# OSO-MISC-21-020_Temperature_GPIO_Board.net
KiCad netlist of a schematic drawn in EAGLE
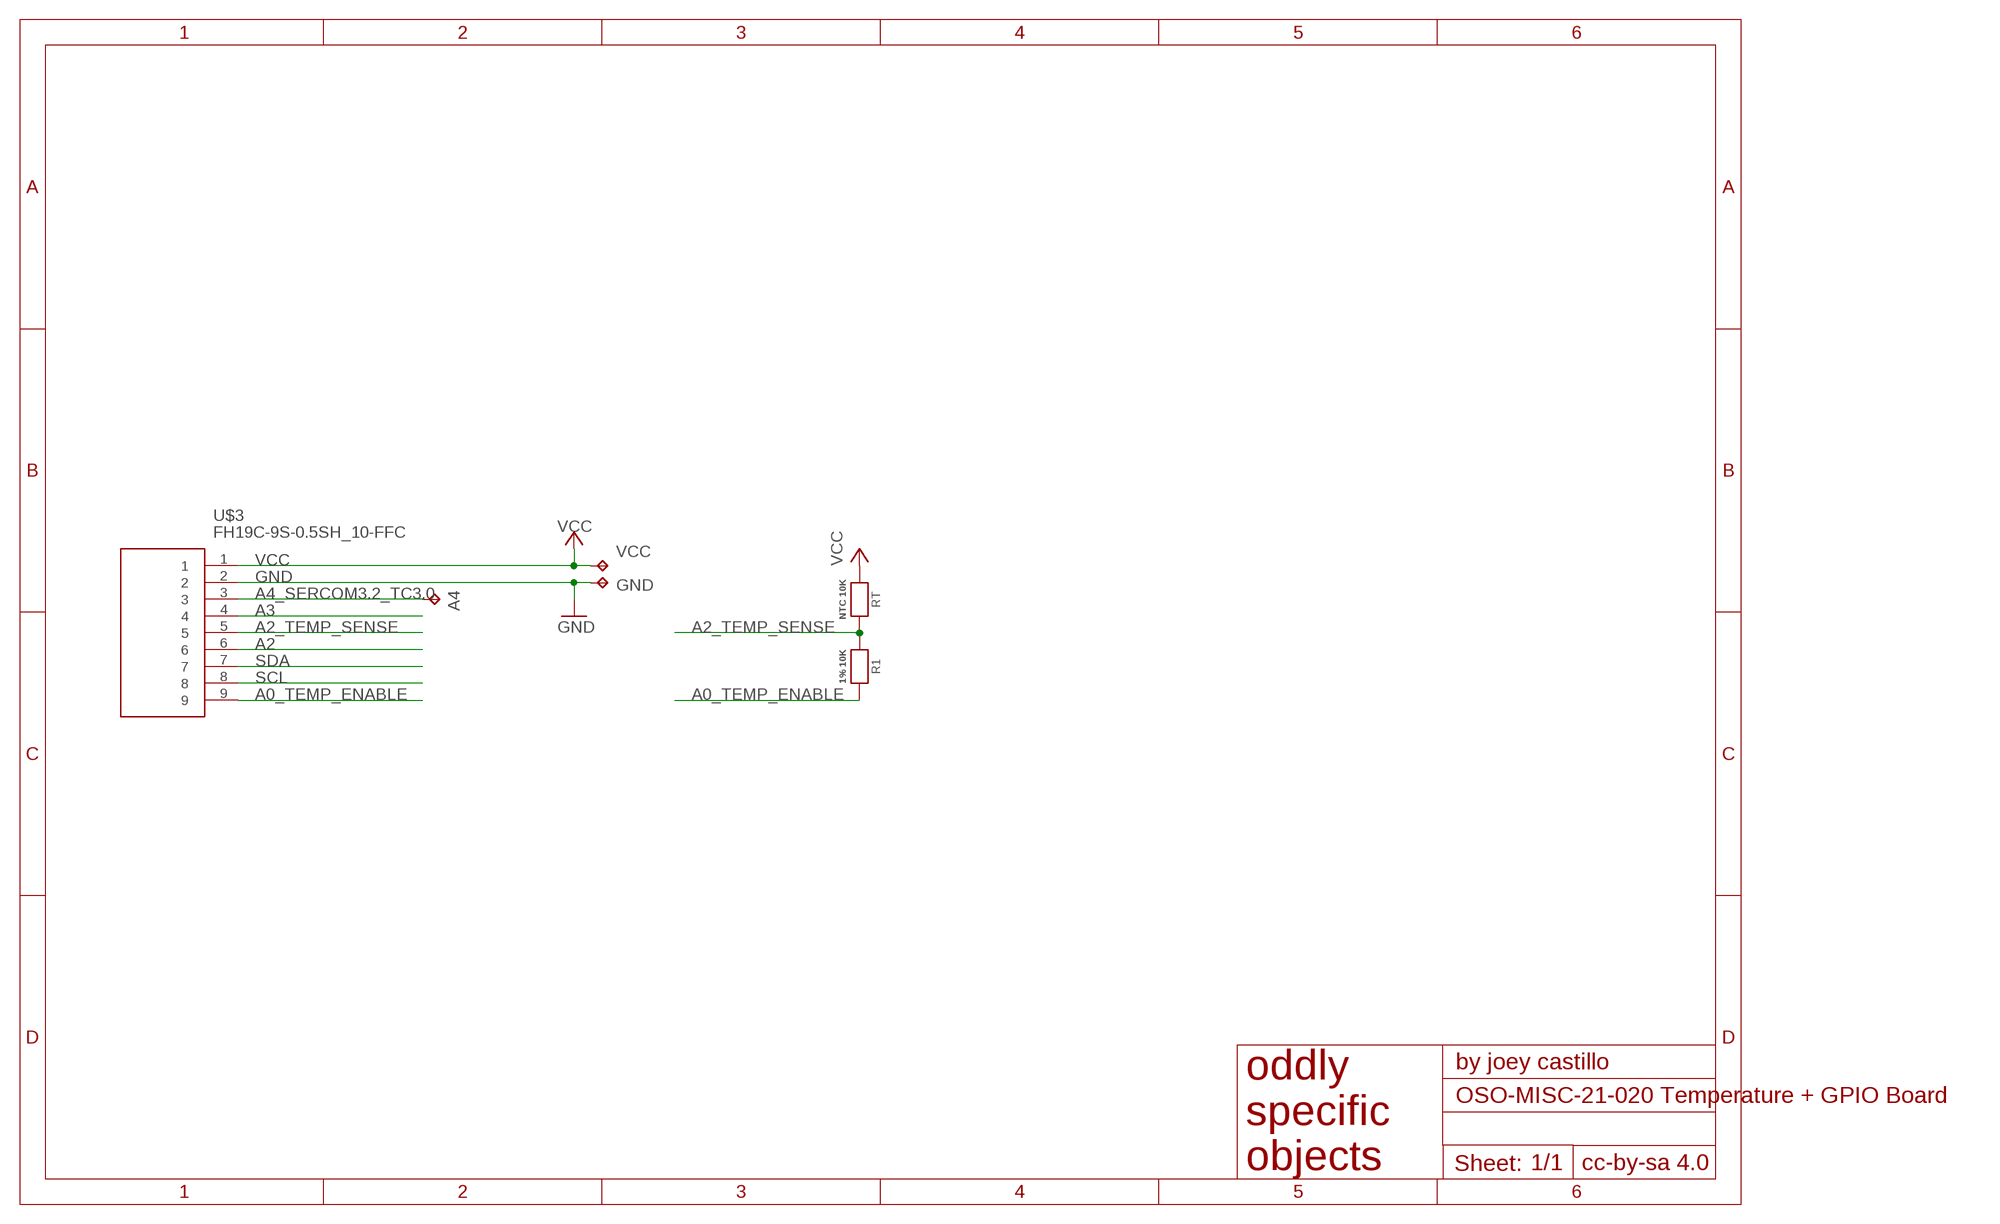
[diagram p0: schematic, sheet 1]

(export (version "E")
  (design (tool "Eeschema 10.0.6"))
  (components
    (comp (ref "A4")
      (value "TPB1,27")
      (footprint "eagle-import:B1,27")
      (libsource (lib "eagle-import") (part "TPB1,27"))
    )
    (comp (ref "GND")
      (value "TPB1,27")
      (footprint "eagle-import:B1,27")
      (libsource (lib "eagle-import") (part "TPB1,27"))
    )
    (comp (ref "R1")
      (value "1% 10K")
      (footprint "eagle-import:_0603MP")
      (libsource (lib "eagle-import") (part "RESISTOR_0603MP"))
    )
    (comp (ref "RT")
      (value "NTC 10K")
      (footprint "eagle-import:_0603")
      (libsource (lib "eagle-import") (part "RESISTOR_0603"))
    )
    (comp (ref "U$3")
      (value "FH19C-9S-0.5SH_10-FFC")
      (footprint "eagle-import:FH19C9S05SH10-FFC")
      (libsource (lib "eagle-import") (part "FH19C-9S-0.5SH_10-FFC"))
    )
    (comp (ref "VCC")
      (value "TPB1,27")
      (footprint "eagle-import:B1,27")
      (libsource (lib "eagle-import") (part "TPB1,27"))
    )
  )
  (nets
    (net (code "1") (name "/A0_TEMP_ENABLE") (class "Default")
      (node (ref "R1") (pin "2") (pinfunction "2_2") (pintype "passive"))
      (node (ref "U$3") (pin "9") (pinfunction "9_9") (pintype "bidirectional"))
    )
    (net (code "2") (name "/A2") (class "Default")
      (node (ref "U$3") (pin "6") (pinfunction "6_6") (pintype "bidirectional"))
    )
    (net (code "3") (name "/A2_TEMP_SENSE") (class "Default")
      (node (ref "R1") (pin "1") (pinfunction "1_1") (pintype "passive"))
      (node (ref "RT") (pin "2") (pinfunction "2_2") (pintype "passive"))
      (node (ref "U$3") (pin "5") (pinfunction "5_5") (pintype "bidirectional"))
    )
    (net (code "4") (name "/A3") (class "Default")
      (node (ref "U$3") (pin "4") (pinfunction "4_4") (pintype "bidirectional"))
    )
    (net (code "5") (name "/A4_SERCOM3.2_TC3.0") (class "Default")
      (node (ref "A4") (pin "TP") (pinfunction "TP_TP") (pintype "input"))
      (node (ref "U$3") (pin "3") (pinfunction "3_3") (pintype "bidirectional"))
    )
    (net (code "6") (name "/SCL") (class "Default")
      (node (ref "U$3") (pin "8") (pinfunction "8_8") (pintype "bidirectional"))
    )
    (net (code "7") (name "/SDA") (class "Default")
      (node (ref "U$3") (pin "7") (pinfunction "7_7") (pintype "bidirectional"))
    )
    (net (code "8") (name "GND") (class "Default")
      (node (ref "GND") (pin "TP") (pinfunction "TP_TP") (pintype "input"))
      (node (ref "U$3") (pin "2") (pinfunction "2_2") (pintype "bidirectional"))
    )
    (net (code "9") (name "VCC") (class "Default")
      (node (ref "RT") (pin "1") (pinfunction "1_1") (pintype "passive"))
      (node (ref "U$3") (pin "1") (pinfunction "1_1") (pintype "bidirectional"))
      (node (ref "VCC") (pin "TP") (pinfunction "TP_TP") (pintype "input"))
    )
  )
)
